# HighVBoard_1_4.net
KiCad netlist of a schematic drawn in EAGLE
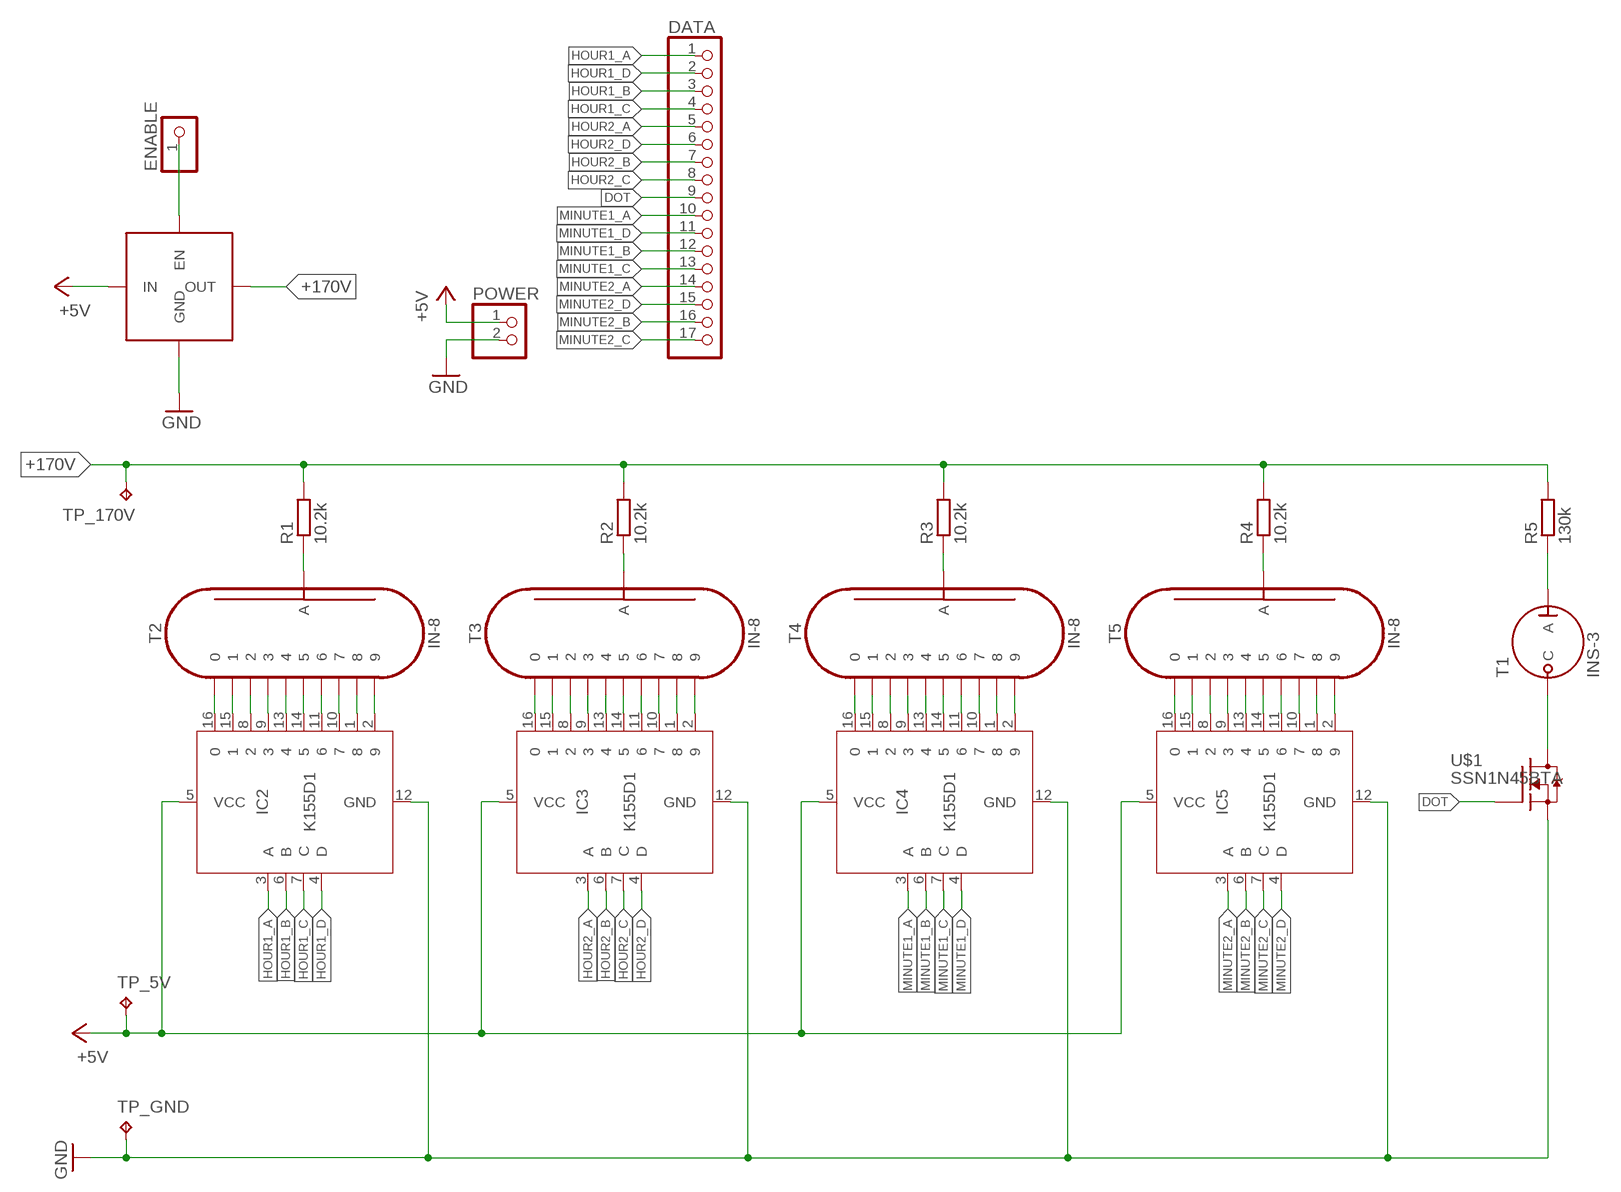
[diagram p0: schematic, sheet 1]

(export (version "E")
  (design (tool "Eeschema 10.0.6"))
  (components
    (comp (ref "DATA")
      (value "PINHD-1X17")
      (footprint "eagle-import:1X17")
      (libsource (lib "eagle-import") (part "PINHD-1X17"))
    )
    (comp (ref "ENABLE")
      (value "PINHD-1X1")
      (footprint "eagle-import:1X01")
      (libsource (lib "eagle-import") (part "PINHD-1X1"))
    )
    (comp (ref "IC2")
      (value "K155D1")
      (footprint "eagle-import:DIL16")
      (libsource (lib "eagle-import") (part "K155D1"))
    )
    (comp (ref "IC3")
      (value "K155D1")
      (footprint "eagle-import:DIL16")
      (libsource (lib "eagle-import") (part "K155D1"))
    )
    (comp (ref "IC4")
      (value "K155D1")
      (footprint "eagle-import:DIL16")
      (libsource (lib "eagle-import") (part "K155D1"))
    )
    (comp (ref "IC5")
      (value "K155D1")
      (footprint "eagle-import:DIL16")
      (libsource (lib "eagle-import") (part "K155D1"))
    )
    (comp (ref "POWER")
      (value "PINHD-1X2")
      (footprint "eagle-import:1X02")
      (libsource (lib "eagle-import") (part "PINHD-1X2"))
    )
    (comp (ref "R1")
      (value "10.2k")
      (footprint "eagle-import:0207_10")
      (libsource (lib "eagle-import") (part "R-EU_0207/10"))
    )
    (comp (ref "R2")
      (value "10.2k")
      (footprint "eagle-import:0207_10")
      (libsource (lib "eagle-import") (part "R-EU_0207/10"))
    )
    (comp (ref "R3")
      (value "10.2k")
      (footprint "eagle-import:0207_10")
      (libsource (lib "eagle-import") (part "R-EU_0207/10"))
    )
    (comp (ref "R4")
      (value "10.2k")
      (footprint "eagle-import:0207_10")
      (libsource (lib "eagle-import") (part "R-EU_0207/10"))
    )
    (comp (ref "R5")
      (value "130k")
      (footprint "eagle-import:0207_10")
      (libsource (lib "eagle-import") (part "R-EU_0207/10"))
    )
    (comp (ref "T1")
      (value "INS-3")
      (footprint "eagle-import:INS-3")
      (libsource (lib "eagle-import") (part "INS-3"))
    )
    (comp (ref "T2")
      (value "IN-8")
      (footprint "eagle-import:IN-8")
      (libsource (lib "eagle-import") (part "IN-8"))
    )
    (comp (ref "T3")
      (value "IN-8")
      (footprint "eagle-import:IN-8")
      (libsource (lib "eagle-import") (part "IN-8"))
    )
    (comp (ref "T4")
      (value "IN-8")
      (footprint "eagle-import:IN-8")
      (libsource (lib "eagle-import") (part "IN-8"))
    )
    (comp (ref "T5")
      (value "IN-8")
      (footprint "eagle-import:IN-8")
      (libsource (lib "eagle-import") (part "IN-8"))
    )
    (comp (ref "TP_5V")
      (value "TPPAD1-13")
      (footprint "eagle-import:P1-13")
      (libsource (lib "eagle-import") (part "TPPAD1-13"))
    )
    (comp (ref "TP_170V")
      (value "TPPAD1-13")
      (footprint "eagle-import:P1-13")
      (libsource (lib "eagle-import") (part "TPPAD1-13"))
    )
    (comp (ref "TP_GND")
      (value "TPPAD1-13")
      (footprint "eagle-import:P1-13")
      (libsource (lib "eagle-import") (part "TPPAD1-13"))
    )
    (comp (ref "U$1")
      (value "SSN1N45BTA")
      (footprint "eagle-import:TO92")
      (libsource (lib "eagle-import") (part "SSN1N45BTA"))
    )
    (comp (ref "U$2")
      (value "NIXIE-PSU")
      (footprint "eagle-import:NIXIE-PSU")
      (libsource (lib "eagle-import") (part "NIXIE-PSU"))
    )
  )
  (nets
    (net (code "1") (name "+5V") (class "Default")
      (node (ref "IC2") (pin "5") (pinfunction "VCC_5") (pintype "bidirectional"))
      (node (ref "IC3") (pin "5") (pinfunction "VCC_5") (pintype "bidirectional"))
      (node (ref "IC4") (pin "5") (pinfunction "VCC_5") (pintype "bidirectional"))
      (node (ref "IC5") (pin "5") (pinfunction "VCC_5") (pintype "bidirectional"))
      (node (ref "POWER") (pin "1") (pinfunction "1_1") (pintype "passive"))
      (node (ref "TP_5V") (pin "TP") (pinfunction "TP_TP") (pintype "input"))
      (node (ref "U$2") (pin "1") (pinfunction "IN_1") (pintype "bidirectional"))
    )
    (net (code "2") (name "+170V") (class "Default")
      (node (ref "R1") (pin "2") (pinfunction "2_2") (pintype "passive"))
      (node (ref "R2") (pin "2") (pinfunction "2_2") (pintype "passive"))
      (node (ref "R3") (pin "2") (pinfunction "2_2") (pintype "passive"))
      (node (ref "R4") (pin "2") (pinfunction "2_2") (pintype "passive"))
      (node (ref "R5") (pin "2") (pinfunction "2_2") (pintype "passive"))
      (node (ref "TP_170V") (pin "TP") (pinfunction "TP_TP") (pintype "input"))
      (node (ref "U$2") (pin "5") (pinfunction "OUT_5") (pintype "bidirectional"))
    )
    (net (code "3") (name "DOT") (class "Default")
      (node (ref "DATA") (pin "9") (pinfunction "9_9") (pintype "passive"))
      (node (ref "U$1") (pin "1") (pinfunction "G_1") (pintype "passive"))
    )
    (net (code "4") (name "GND") (class "Default")
      (node (ref "IC2") (pin "12") (pinfunction "GND_12") (pintype "bidirectional"))
      (node (ref "IC3") (pin "12") (pinfunction "GND_12") (pintype "bidirectional"))
      (node (ref "IC4") (pin "12") (pinfunction "GND_12") (pintype "bidirectional"))
      (node (ref "IC5") (pin "12") (pinfunction "GND_12") (pintype "bidirectional"))
      (node (ref "POWER") (pin "2") (pinfunction "2_2") (pintype "passive"))
      (node (ref "TP_GND") (pin "TP") (pinfunction "TP_TP") (pintype "input"))
      (node (ref "U$1") (pin "3") (pinfunction "S_3") (pintype "passive"))
      (node (ref "U$2") (pin "2") (pinfunction "GND_2") (pintype "bidirectional"))
      (node (ref "U$2") (pin "4") (pinfunction "GND_4") (pintype "bidirectional"))
    )
    (net (code "5") (name "HOUR1_A") (class "Default")
      (node (ref "DATA") (pin "1") (pinfunction "1_1") (pintype "passive"))
      (node (ref "IC2") (pin "3") (pinfunction "A_3") (pintype "bidirectional"))
    )
    (net (code "6") (name "HOUR1_B") (class "Default")
      (node (ref "DATA") (pin "3") (pinfunction "3_3") (pintype "passive"))
      (node (ref "IC2") (pin "6") (pinfunction "B_6") (pintype "bidirectional"))
    )
    (net (code "7") (name "HOUR1_C") (class "Default")
      (node (ref "DATA") (pin "4") (pinfunction "4_4") (pintype "passive"))
      (node (ref "IC2") (pin "7") (pinfunction "C_7") (pintype "bidirectional"))
    )
    (net (code "8") (name "HOUR1_D") (class "Default")
      (node (ref "DATA") (pin "2") (pinfunction "2_2") (pintype "passive"))
      (node (ref "IC2") (pin "4") (pinfunction "D_4") (pintype "bidirectional"))
    )
    (net (code "9") (name "HOUR2_A") (class "Default")
      (node (ref "DATA") (pin "5") (pinfunction "5_5") (pintype "passive"))
      (node (ref "IC3") (pin "3") (pinfunction "A_3") (pintype "bidirectional"))
    )
    (net (code "10") (name "HOUR2_B") (class "Default")
      (node (ref "DATA") (pin "7") (pinfunction "7_7") (pintype "passive"))
      (node (ref "IC3") (pin "6") (pinfunction "B_6") (pintype "bidirectional"))
    )
    (net (code "11") (name "HOUR2_C") (class "Default")
      (node (ref "DATA") (pin "8") (pinfunction "8_8") (pintype "passive"))
      (node (ref "IC3") (pin "7") (pinfunction "C_7") (pintype "bidirectional"))
    )
    (net (code "12") (name "HOUR2_D") (class "Default")
      (node (ref "DATA") (pin "6") (pinfunction "6_6") (pintype "passive"))
      (node (ref "IC3") (pin "4") (pinfunction "D_4") (pintype "bidirectional"))
    )
    (net (code "13") (name "MINUTE1_A") (class "Default")
      (node (ref "DATA") (pin "10") (pinfunction "10_10") (pintype "passive"))
      (node (ref "IC4") (pin "3") (pinfunction "A_3") (pintype "bidirectional"))
    )
    (net (code "14") (name "MINUTE1_B") (class "Default")
      (node (ref "DATA") (pin "12") (pinfunction "12_12") (pintype "passive"))
      (node (ref "IC4") (pin "6") (pinfunction "B_6") (pintype "bidirectional"))
    )
    (net (code "15") (name "MINUTE1_C") (class "Default")
      (node (ref "DATA") (pin "13") (pinfunction "13_13") (pintype "passive"))
      (node (ref "IC4") (pin "7") (pinfunction "C_7") (pintype "bidirectional"))
    )
    (net (code "16") (name "MINUTE1_D") (class "Default")
      (node (ref "DATA") (pin "11") (pinfunction "11_11") (pintype "passive"))
      (node (ref "IC4") (pin "4") (pinfunction "D_4") (pintype "bidirectional"))
    )
    (net (code "17") (name "MINUTE2_A") (class "Default")
      (node (ref "DATA") (pin "14") (pinfunction "14_14") (pintype "passive"))
      (node (ref "IC5") (pin "3") (pinfunction "A_3") (pintype "bidirectional"))
    )
    (net (code "18") (name "MINUTE2_B") (class "Default")
      (node (ref "DATA") (pin "16") (pinfunction "16_16") (pintype "passive"))
      (node (ref "IC5") (pin "6") (pinfunction "B_6") (pintype "bidirectional"))
    )
    (net (code "19") (name "MINUTE2_C") (class "Default")
      (node (ref "DATA") (pin "17") (pinfunction "17_17") (pintype "passive"))
      (node (ref "IC5") (pin "7") (pinfunction "C_7") (pintype "bidirectional"))
    )
    (net (code "20") (name "MINUTE2_D") (class "Default")
      (node (ref "DATA") (pin "15") (pinfunction "15_15") (pintype "passive"))
      (node (ref "IC5") (pin "4") (pinfunction "D_4") (pintype "bidirectional"))
    )
    (net (code "21") (name "Net-(IC2-0)") (class "Default")
      (node (ref "IC2") (pin "16") (pinfunction "0_16") (pintype "bidirectional"))
      (node (ref "T2") (pin "10") (pinfunction "0_10") (pintype "bidirectional"))
    )
    (net (code "22") (name "Net-(IC2-1)") (class "Default")
      (node (ref "IC2") (pin "15") (pinfunction "1_15") (pintype "bidirectional"))
      (node (ref "T2") (pin "1") (pinfunction "1_1") (pintype "bidirectional"))
    )
    (net (code "23") (name "Net-(IC2-2)") (class "Default")
      (node (ref "IC2") (pin "8") (pinfunction "2_8") (pintype "bidirectional"))
      (node (ref "T2") (pin "2") (pinfunction "2_2") (pintype "bidirectional"))
    )
    (net (code "24") (name "Net-(IC2-3)") (class "Default")
      (node (ref "IC2") (pin "9") (pinfunction "3_9") (pintype "bidirectional"))
      (node (ref "T2") (pin "3") (pinfunction "3_3") (pintype "bidirectional"))
    )
    (net (code "25") (name "Net-(IC2-4)") (class "Default")
      (node (ref "IC2") (pin "13") (pinfunction "4_13") (pintype "bidirectional"))
      (node (ref "T2") (pin "4") (pinfunction "4_4") (pintype "bidirectional"))
    )
    (net (code "26") (name "Net-(IC2-5)") (class "Default")
      (node (ref "IC2") (pin "14") (pinfunction "5_14") (pintype "bidirectional"))
      (node (ref "T2") (pin "5") (pinfunction "5_5") (pintype "bidirectional"))
    )
    (net (code "27") (name "Net-(IC2-6)") (class "Default")
      (node (ref "IC2") (pin "11") (pinfunction "6_11") (pintype "bidirectional"))
      (node (ref "T2") (pin "6") (pinfunction "6_6") (pintype "bidirectional"))
    )
    (net (code "28") (name "Net-(IC2-7)") (class "Default")
      (node (ref "IC2") (pin "10") (pinfunction "7_10") (pintype "bidirectional"))
      (node (ref "T2") (pin "7") (pinfunction "7_7") (pintype "bidirectional"))
    )
    (net (code "29") (name "Net-(IC2-8)") (class "Default")
      (node (ref "IC2") (pin "1") (pinfunction "8_1") (pintype "bidirectional"))
      (node (ref "T2") (pin "8") (pinfunction "8_8") (pintype "bidirectional"))
    )
    (net (code "30") (name "Net-(IC2-9)") (class "Default")
      (node (ref "IC2") (pin "2") (pinfunction "9_2") (pintype "bidirectional"))
      (node (ref "T2") (pin "9") (pinfunction "9_9") (pintype "bidirectional"))
    )
    (net (code "31") (name "Net-(IC3-0)") (class "Default")
      (node (ref "IC3") (pin "16") (pinfunction "0_16") (pintype "bidirectional"))
      (node (ref "T3") (pin "10") (pinfunction "0_10") (pintype "bidirectional"))
    )
    (net (code "32") (name "Net-(IC3-1)") (class "Default")
      (node (ref "IC3") (pin "15") (pinfunction "1_15") (pintype "bidirectional"))
      (node (ref "T3") (pin "1") (pinfunction "1_1") (pintype "bidirectional"))
    )
    (net (code "33") (name "Net-(IC3-2)") (class "Default")
      (node (ref "IC3") (pin "8") (pinfunction "2_8") (pintype "bidirectional"))
      (node (ref "T3") (pin "2") (pinfunction "2_2") (pintype "bidirectional"))
    )
    (net (code "34") (name "Net-(IC3-3)") (class "Default")
      (node (ref "IC3") (pin "9") (pinfunction "3_9") (pintype "bidirectional"))
      (node (ref "T3") (pin "3") (pinfunction "3_3") (pintype "bidirectional"))
    )
    (net (code "35") (name "Net-(IC3-4)") (class "Default")
      (node (ref "IC3") (pin "13") (pinfunction "4_13") (pintype "bidirectional"))
      (node (ref "T3") (pin "4") (pinfunction "4_4") (pintype "bidirectional"))
    )
    (net (code "36") (name "Net-(IC3-5)") (class "Default")
      (node (ref "IC3") (pin "14") (pinfunction "5_14") (pintype "bidirectional"))
      (node (ref "T3") (pin "5") (pinfunction "5_5") (pintype "bidirectional"))
    )
    (net (code "37") (name "Net-(IC3-6)") (class "Default")
      (node (ref "IC3") (pin "11") (pinfunction "6_11") (pintype "bidirectional"))
      (node (ref "T3") (pin "6") (pinfunction "6_6") (pintype "bidirectional"))
    )
    (net (code "38") (name "Net-(IC3-7)") (class "Default")
      (node (ref "IC3") (pin "10") (pinfunction "7_10") (pintype "bidirectional"))
      (node (ref "T3") (pin "7") (pinfunction "7_7") (pintype "bidirectional"))
    )
    (net (code "39") (name "Net-(IC3-8)") (class "Default")
      (node (ref "IC3") (pin "1") (pinfunction "8_1") (pintype "bidirectional"))
      (node (ref "T3") (pin "8") (pinfunction "8_8") (pintype "bidirectional"))
    )
    (net (code "40") (name "Net-(IC3-9)") (class "Default")
      (node (ref "IC3") (pin "2") (pinfunction "9_2") (pintype "bidirectional"))
      (node (ref "T3") (pin "9") (pinfunction "9_9") (pintype "bidirectional"))
    )
    (net (code "41") (name "Net-(IC4-0)") (class "Default")
      (node (ref "IC4") (pin "16") (pinfunction "0_16") (pintype "bidirectional"))
      (node (ref "T4") (pin "10") (pinfunction "0_10") (pintype "bidirectional"))
    )
    (net (code "42") (name "Net-(IC4-1)") (class "Default")
      (node (ref "IC4") (pin "15") (pinfunction "1_15") (pintype "bidirectional"))
      (node (ref "T4") (pin "1") (pinfunction "1_1") (pintype "bidirectional"))
    )
    (net (code "43") (name "Net-(IC4-2)") (class "Default")
      (node (ref "IC4") (pin "8") (pinfunction "2_8") (pintype "bidirectional"))
      (node (ref "T4") (pin "2") (pinfunction "2_2") (pintype "bidirectional"))
    )
    (net (code "44") (name "Net-(IC4-3)") (class "Default")
      (node (ref "IC4") (pin "9") (pinfunction "3_9") (pintype "bidirectional"))
      (node (ref "T4") (pin "3") (pinfunction "3_3") (pintype "bidirectional"))
    )
    (net (code "45") (name "Net-(IC4-4)") (class "Default")
      (node (ref "IC4") (pin "13") (pinfunction "4_13") (pintype "bidirectional"))
      (node (ref "T4") (pin "4") (pinfunction "4_4") (pintype "bidirectional"))
    )
    (net (code "46") (name "Net-(IC4-5)") (class "Default")
      (node (ref "IC4") (pin "14") (pinfunction "5_14") (pintype "bidirectional"))
      (node (ref "T4") (pin "5") (pinfunction "5_5") (pintype "bidirectional"))
    )
    (net (code "47") (name "Net-(IC4-6)") (class "Default")
      (node (ref "IC4") (pin "11") (pinfunction "6_11") (pintype "bidirectional"))
      (node (ref "T4") (pin "6") (pinfunction "6_6") (pintype "bidirectional"))
    )
    (net (code "48") (name "Net-(IC4-7)") (class "Default")
      (node (ref "IC4") (pin "10") (pinfunction "7_10") (pintype "bidirectional"))
      (node (ref "T4") (pin "7") (pinfunction "7_7") (pintype "bidirectional"))
    )
    (net (code "49") (name "Net-(IC4-8)") (class "Default")
      (node (ref "IC4") (pin "1") (pinfunction "8_1") (pintype "bidirectional"))
      (node (ref "T4") (pin "8") (pinfunction "8_8") (pintype "bidirectional"))
    )
    (net (code "50") (name "Net-(IC4-9)") (class "Default")
      (node (ref "IC4") (pin "2") (pinfunction "9_2") (pintype "bidirectional"))
      (node (ref "T4") (pin "9") (pinfunction "9_9") (pintype "bidirectional"))
    )
    (net (code "51") (name "Net-(IC5-0)") (class "Default")
      (node (ref "IC5") (pin "16") (pinfunction "0_16") (pintype "bidirectional"))
      (node (ref "T5") (pin "10") (pinfunction "0_10") (pintype "bidirectional"))
    )
    (net (code "52") (name "Net-(IC5-1)") (class "Default")
      (node (ref "IC5") (pin "15") (pinfunction "1_15") (pintype "bidirectional"))
      (node (ref "T5") (pin "1") (pinfunction "1_1") (pintype "bidirectional"))
    )
    (net (code "53") (name "Net-(IC5-2)") (class "Default")
      (node (ref "IC5") (pin "8") (pinfunction "2_8") (pintype "bidirectional"))
      (node (ref "T5") (pin "2") (pinfunction "2_2") (pintype "bidirectional"))
    )
    (net (code "54") (name "Net-(IC5-3)") (class "Default")
      (node (ref "IC5") (pin "9") (pinfunction "3_9") (pintype "bidirectional"))
      (node (ref "T5") (pin "3") (pinfunction "3_3") (pintype "bidirectional"))
    )
    (net (code "55") (name "Net-(IC5-4)") (class "Default")
      (node (ref "IC5") (pin "13") (pinfunction "4_13") (pintype "bidirectional"))
      (node (ref "T5") (pin "4") (pinfunction "4_4") (pintype "bidirectional"))
    )
    (net (code "56") (name "Net-(IC5-5)") (class "Default")
      (node (ref "IC5") (pin "14") (pinfunction "5_14") (pintype "bidirectional"))
      (node (ref "T5") (pin "5") (pinfunction "5_5") (pintype "bidirectional"))
    )
    (net (code "57") (name "Net-(IC5-6)") (class "Default")
      (node (ref "IC5") (pin "11") (pinfunction "6_11") (pintype "bidirectional"))
      (node (ref "T5") (pin "6") (pinfunction "6_6") (pintype "bidirectional"))
    )
    (net (code "58") (name "Net-(IC5-7)") (class "Default")
      (node (ref "IC5") (pin "10") (pinfunction "7_10") (pintype "bidirectional"))
      (node (ref "T5") (pin "7") (pinfunction "7_7") (pintype "bidirectional"))
    )
    (net (code "59") (name "Net-(IC5-8)") (class "Default")
      (node (ref "IC5") (pin "1") (pinfunction "8_1") (pintype "bidirectional"))
      (node (ref "T5") (pin "8") (pinfunction "8_8") (pintype "bidirectional"))
    )
    (net (code "60") (name "Net-(IC5-9)") (class "Default")
      (node (ref "IC5") (pin "2") (pinfunction "9_2") (pintype "bidirectional"))
      (node (ref "T5") (pin "9") (pinfunction "9_9") (pintype "bidirectional"))
    )
    (net (code "61") (name "Net-(R1-Pad1)") (class "Default")
      (node (ref "R1") (pin "1") (pinfunction "1_1") (pintype "passive"))
      (node (ref "T2") (pin "A") (pinfunction "A_A") (pintype "bidirectional"))
    )
    (net (code "62") (name "Net-(R2-Pad1)") (class "Default")
      (node (ref "R2") (pin "1") (pinfunction "1_1") (pintype "passive"))
      (node (ref "T3") (pin "A") (pinfunction "A_A") (pintype "bidirectional"))
    )
    (net (code "63") (name "Net-(R3-Pad1)") (class "Default")
      (node (ref "R3") (pin "1") (pinfunction "1_1") (pintype "passive"))
      (node (ref "T4") (pin "A") (pinfunction "A_A") (pintype "bidirectional"))
    )
    (net (code "64") (name "Net-(R4-Pad1)") (class "Default")
      (node (ref "R4") (pin "1") (pinfunction "1_1") (pintype "passive"))
      (node (ref "T5") (pin "A") (pinfunction "A_A") (pintype "bidirectional"))
    )
    (net (code "65") (name "Net-(R5-Pad1)") (class "Default")
      (node (ref "R5") (pin "1") (pinfunction "1_1") (pintype "passive"))
      (node (ref "T1") (pin "A") (pinfunction "A_A") (pintype "bidirectional"))
    )
    (net (code "66") (name "Net-(U$1-D)") (class "Default")
      (node (ref "T1") (pin "C") (pinfunction "C_C") (pintype "bidirectional"))
      (node (ref "U$1") (pin "2") (pinfunction "D_2") (pintype "passive"))
    )
    (net (code "67") (name "Net-(U$2-EN)") (class "Default")
      (node (ref "ENABLE") (pin "1") (pinfunction "1_1") (pintype "passive"))
      (node (ref "U$2") (pin "3") (pinfunction "EN_3") (pintype "bidirectional"))
    )
  )
)
